# ForceBoard.net
KiCad netlist of a schematic drawn in EAGLE
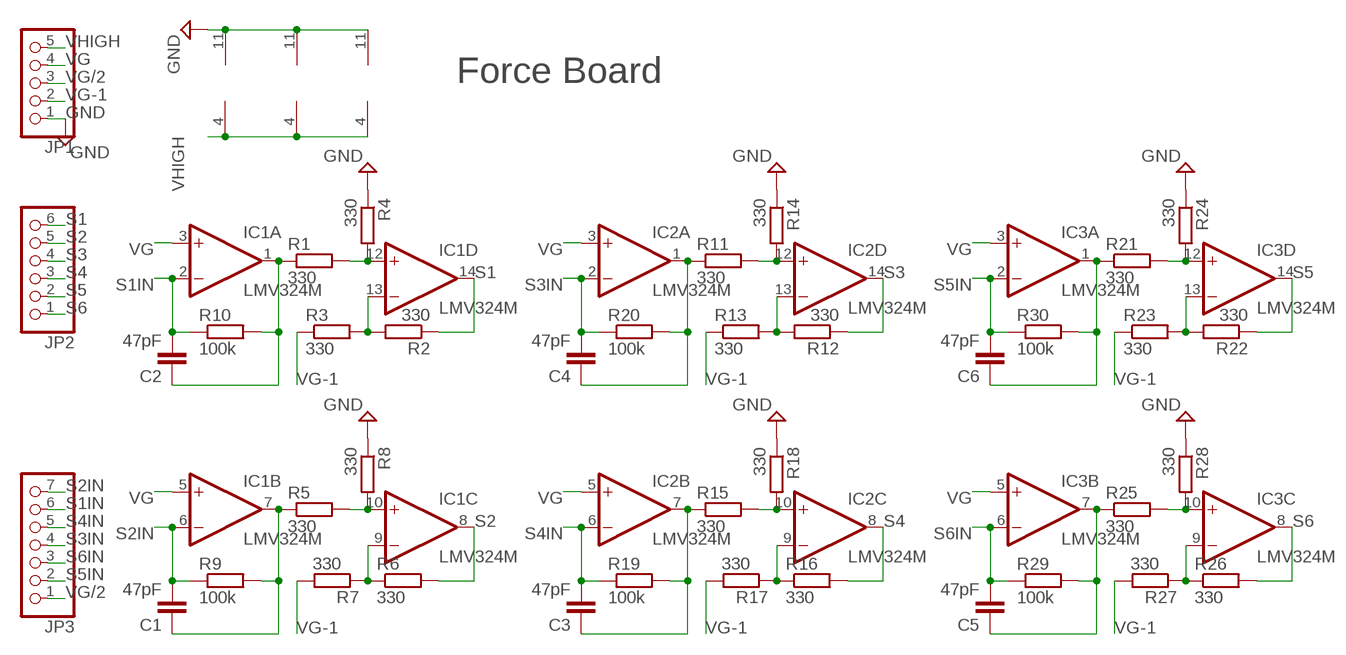
[diagram p0: schematic, sheet 1]

(export (version "E")
  (design (tool "Eeschema 10.0.6"))
  (components
    (comp (ref "C1")
      (value "47pF")
      (footprint "eagle-import:C0805")
      (libsource (lib "eagle-import") (part "C-EUC0805"))
    )
    (comp (ref "C2")
      (value "47pF")
      (footprint "eagle-import:C0805")
      (libsource (lib "eagle-import") (part "C-EUC0805"))
    )
    (comp (ref "C3")
      (value "47pF")
      (footprint "eagle-import:C0805")
      (libsource (lib "eagle-import") (part "C-EUC0805"))
    )
    (comp (ref "C4")
      (value "47pF")
      (footprint "eagle-import:C0805")
      (libsource (lib "eagle-import") (part "C-EUC0805"))
    )
    (comp (ref "C5")
      (value "47pF")
      (footprint "eagle-import:C0805")
      (libsource (lib "eagle-import") (part "C-EUC0805"))
    )
    (comp (ref "C6")
      (value "47pF")
      (footprint "eagle-import:C0805")
      (libsource (lib "eagle-import") (part "C-EUC0805"))
    )
    (comp (ref "IC1")
      (value "LMV324M")
      (footprint "eagle-import:SO14")
      (libsource (lib "eagle-import") (part "LMV324?M"))
    )
    (comp (ref "IC2")
      (value "LMV324M")
      (footprint "eagle-import:SO14")
      (libsource (lib "eagle-import") (part "LMV324?M"))
    )
    (comp (ref "IC3")
      (value "LMV324M")
      (footprint "eagle-import:SO14")
      (libsource (lib "eagle-import") (part "LMV324?M"))
    )
    (comp (ref "JP1")
      (value "PINHD-1X5")
      (footprint "eagle-import:1X05")
      (libsource (lib "eagle-import") (part "PINHD-1X5"))
    )
    (comp (ref "JP2")
      (value "PINHD-1X6")
      (footprint "eagle-import:1X06")
      (libsource (lib "eagle-import") (part "PINHD-1X6"))
    )
    (comp (ref "JP3")
      (value "PINHD-1X7")
      (footprint "eagle-import:1X07")
      (libsource (lib "eagle-import") (part "PINHD-1X7"))
    )
    (comp (ref "R1")
      (value "330")
      (footprint "eagle-import:R0805")
      (libsource (lib "eagle-import") (part "R-EU_R0805"))
    )
    (comp (ref "R2")
      (value "330")
      (footprint "eagle-import:R0805")
      (libsource (lib "eagle-import") (part "R-EU_R0805"))
    )
    (comp (ref "R3")
      (value "330")
      (footprint "eagle-import:R0805")
      (libsource (lib "eagle-import") (part "R-EU_R0805"))
    )
    (comp (ref "R4")
      (value "330")
      (footprint "eagle-import:R0805")
      (libsource (lib "eagle-import") (part "R-EU_R0805"))
    )
    (comp (ref "R5")
      (value "330")
      (footprint "eagle-import:R0805")
      (libsource (lib "eagle-import") (part "R-EU_R0805"))
    )
    (comp (ref "R6")
      (value "330")
      (footprint "eagle-import:R0805")
      (libsource (lib "eagle-import") (part "R-EU_R0805"))
    )
    (comp (ref "R7")
      (value "330")
      (footprint "eagle-import:R0805")
      (libsource (lib "eagle-import") (part "R-EU_R0805"))
    )
    (comp (ref "R8")
      (value "330")
      (footprint "eagle-import:R0805")
      (libsource (lib "eagle-import") (part "R-EU_R0805"))
    )
    (comp (ref "R9")
      (value "100k")
      (footprint "eagle-import:R0805")
      (libsource (lib "eagle-import") (part "R-EU_R0805"))
    )
    (comp (ref "R10")
      (value "100k")
      (footprint "eagle-import:R0805")
      (libsource (lib "eagle-import") (part "R-EU_R0805"))
    )
    (comp (ref "R11")
      (value "330")
      (footprint "eagle-import:R0805")
      (libsource (lib "eagle-import") (part "R-EU_R0805"))
    )
    (comp (ref "R12")
      (value "330")
      (footprint "eagle-import:R0805")
      (libsource (lib "eagle-import") (part "R-EU_R0805"))
    )
    (comp (ref "R13")
      (value "330")
      (footprint "eagle-import:R0805")
      (libsource (lib "eagle-import") (part "R-EU_R0805"))
    )
    (comp (ref "R14")
      (value "330")
      (footprint "eagle-import:R0805")
      (libsource (lib "eagle-import") (part "R-EU_R0805"))
    )
    (comp (ref "R15")
      (value "330")
      (footprint "eagle-import:R0805")
      (libsource (lib "eagle-import") (part "R-EU_R0805"))
    )
    (comp (ref "R16")
      (value "330")
      (footprint "eagle-import:R0805")
      (libsource (lib "eagle-import") (part "R-EU_R0805"))
    )
    (comp (ref "R17")
      (value "330")
      (footprint "eagle-import:R0805")
      (libsource (lib "eagle-import") (part "R-EU_R0805"))
    )
    (comp (ref "R18")
      (value "330")
      (footprint "eagle-import:R0805")
      (libsource (lib "eagle-import") (part "R-EU_R0805"))
    )
    (comp (ref "R19")
      (value "100k")
      (footprint "eagle-import:R0805")
      (libsource (lib "eagle-import") (part "R-EU_R0805"))
    )
    (comp (ref "R20")
      (value "100k")
      (footprint "eagle-import:R0805")
      (libsource (lib "eagle-import") (part "R-EU_R0805"))
    )
    (comp (ref "R21")
      (value "330")
      (footprint "eagle-import:R0805")
      (libsource (lib "eagle-import") (part "R-EU_R0805"))
    )
    (comp (ref "R22")
      (value "330")
      (footprint "eagle-import:R0805")
      (libsource (lib "eagle-import") (part "R-EU_R0805"))
    )
    (comp (ref "R23")
      (value "330")
      (footprint "eagle-import:R0805")
      (libsource (lib "eagle-import") (part "R-EU_R0805"))
    )
    (comp (ref "R24")
      (value "330")
      (footprint "eagle-import:R0805")
      (libsource (lib "eagle-import") (part "R-EU_R0805"))
    )
    (comp (ref "R25")
      (value "330")
      (footprint "eagle-import:R0805")
      (libsource (lib "eagle-import") (part "R-EU_R0805"))
    )
    (comp (ref "R26")
      (value "330")
      (footprint "eagle-import:R0805")
      (libsource (lib "eagle-import") (part "R-EU_R0805"))
    )
    (comp (ref "R27")
      (value "330")
      (footprint "eagle-import:R0805")
      (libsource (lib "eagle-import") (part "R-EU_R0805"))
    )
    (comp (ref "R28")
      (value "330")
      (footprint "eagle-import:R0805")
      (libsource (lib "eagle-import") (part "R-EU_R0805"))
    )
    (comp (ref "R29")
      (value "100k")
      (footprint "eagle-import:R0805")
      (libsource (lib "eagle-import") (part "R-EU_R0805"))
    )
    (comp (ref "R30")
      (value "100k")
      (footprint "eagle-import:R0805")
      (libsource (lib "eagle-import") (part "R-EU_R0805"))
    )
  )
  (nets
    (net (code "1") (name "/S1") (class "Default")
      (node (ref "IC1") (pin "14") (pinfunction "OUT_14") (pintype "output"))
      (node (ref "JP2") (pin "6") (pinfunction "6_6") (pintype "passive"))
      (node (ref "R2") (pin "1") (pinfunction "1_1") (pintype "passive"))
    )
    (net (code "2") (name "/S1IN") (class "Default")
      (node (ref "C2") (pin "2") (pinfunction "2_2") (pintype "passive"))
      (node (ref "IC1") (pin "2") (pinfunction "-IN_2") (pintype "input"))
      (node (ref "JP3") (pin "6") (pinfunction "6_6") (pintype "passive"))
      (node (ref "R10") (pin "1") (pinfunction "1_1") (pintype "passive"))
    )
    (net (code "3") (name "/S2") (class "Default")
      (node (ref "IC1") (pin "8") (pinfunction "OUT_8") (pintype "output"))
      (node (ref "JP2") (pin "5") (pinfunction "5_5") (pintype "passive"))
      (node (ref "R6") (pin "2") (pinfunction "2_2") (pintype "passive"))
    )
    (net (code "4") (name "/S2IN") (class "Default")
      (node (ref "C1") (pin "2") (pinfunction "2_2") (pintype "passive"))
      (node (ref "IC1") (pin "6") (pinfunction "-IN_6") (pintype "input"))
      (node (ref "JP3") (pin "7") (pinfunction "7_7") (pintype "passive"))
      (node (ref "R9") (pin "1") (pinfunction "1_1") (pintype "passive"))
    )
    (net (code "5") (name "/S3") (class "Default")
      (node (ref "IC2") (pin "14") (pinfunction "OUT_14") (pintype "output"))
      (node (ref "JP2") (pin "4") (pinfunction "4_4") (pintype "passive"))
      (node (ref "R12") (pin "1") (pinfunction "1_1") (pintype "passive"))
    )
    (net (code "6") (name "/S3IN") (class "Default")
      (node (ref "C4") (pin "2") (pinfunction "2_2") (pintype "passive"))
      (node (ref "IC2") (pin "2") (pinfunction "-IN_2") (pintype "input"))
      (node (ref "JP3") (pin "4") (pinfunction "4_4") (pintype "passive"))
      (node (ref "R20") (pin "1") (pinfunction "1_1") (pintype "passive"))
    )
    (net (code "7") (name "/S4") (class "Default")
      (node (ref "IC2") (pin "8") (pinfunction "OUT_8") (pintype "output"))
      (node (ref "JP2") (pin "3") (pinfunction "3_3") (pintype "passive"))
      (node (ref "R16") (pin "2") (pinfunction "2_2") (pintype "passive"))
    )
    (net (code "8") (name "/S4IN") (class "Default")
      (node (ref "C3") (pin "2") (pinfunction "2_2") (pintype "passive"))
      (node (ref "IC2") (pin "6") (pinfunction "-IN_6") (pintype "input"))
      (node (ref "JP3") (pin "5") (pinfunction "5_5") (pintype "passive"))
      (node (ref "R19") (pin "1") (pinfunction "1_1") (pintype "passive"))
    )
    (net (code "9") (name "/S5") (class "Default")
      (node (ref "IC3") (pin "14") (pinfunction "OUT_14") (pintype "output"))
      (node (ref "JP2") (pin "2") (pinfunction "2_2") (pintype "passive"))
      (node (ref "R22") (pin "1") (pinfunction "1_1") (pintype "passive"))
    )
    (net (code "10") (name "/S5IN") (class "Default")
      (node (ref "C6") (pin "2") (pinfunction "2_2") (pintype "passive"))
      (node (ref "IC3") (pin "2") (pinfunction "-IN_2") (pintype "input"))
      (node (ref "JP3") (pin "2") (pinfunction "2_2") (pintype "passive"))
      (node (ref "R30") (pin "1") (pinfunction "1_1") (pintype "passive"))
    )
    (net (code "11") (name "/S6") (class "Default")
      (node (ref "IC3") (pin "8") (pinfunction "OUT_8") (pintype "output"))
      (node (ref "JP2") (pin "1") (pinfunction "1_1") (pintype "passive"))
      (node (ref "R26") (pin "2") (pinfunction "2_2") (pintype "passive"))
    )
    (net (code "12") (name "/S6IN") (class "Default")
      (node (ref "C5") (pin "2") (pinfunction "2_2") (pintype "passive"))
      (node (ref "IC3") (pin "6") (pinfunction "-IN_6") (pintype "input"))
      (node (ref "JP3") (pin "3") (pinfunction "3_3") (pintype "passive"))
      (node (ref "R29") (pin "1") (pinfunction "1_1") (pintype "passive"))
    )
    (net (code "13") (name "/VG") (class "Default")
      (node (ref "IC1") (pin "3") (pinfunction "+IN_3") (pintype "input"))
      (node (ref "IC1") (pin "5") (pinfunction "+IN_5") (pintype "input"))
      (node (ref "IC2") (pin "3") (pinfunction "+IN_3") (pintype "input"))
      (node (ref "IC2") (pin "5") (pinfunction "+IN_5") (pintype "input"))
      (node (ref "IC3") (pin "3") (pinfunction "+IN_3") (pintype "input"))
      (node (ref "IC3") (pin "5") (pinfunction "+IN_5") (pintype "input"))
      (node (ref "JP1") (pin "4") (pinfunction "4_4") (pintype "passive"))
    )
    (net (code "14") (name "/VG-1") (class "Default")
      (node (ref "JP1") (pin "2") (pinfunction "2_2") (pintype "passive"))
      (node (ref "R13") (pin "1") (pinfunction "1_1") (pintype "passive"))
      (node (ref "R17") (pin "2") (pinfunction "2_2") (pintype "passive"))
      (node (ref "R23") (pin "1") (pinfunction "1_1") (pintype "passive"))
      (node (ref "R27") (pin "2") (pinfunction "2_2") (pintype "passive"))
      (node (ref "R3") (pin "1") (pinfunction "1_1") (pintype "passive"))
      (node (ref "R7") (pin "2") (pinfunction "2_2") (pintype "passive"))
    )
    (net (code "15") (name "/VG{slash}2") (class "Default")
      (node (ref "JP1") (pin "3") (pinfunction "3_3") (pintype "passive"))
      (node (ref "JP3") (pin "1") (pinfunction "1_1") (pintype "passive"))
    )
    (net (code "16") (name "/VHIGH") (class "Default")
      (node (ref "IC1") (pin "4") (pinfunction "V+_4") (pintype "power_in"))
      (node (ref "IC2") (pin "4") (pinfunction "V+_4") (pintype "power_in"))
      (node (ref "IC3") (pin "4") (pinfunction "V+_4") (pintype "power_in"))
      (node (ref "JP1") (pin "5") (pinfunction "5_5") (pintype "passive"))
    )
    (net (code "17") (name "GND") (class "Default")
      (node (ref "IC1") (pin "11") (pinfunction "V-_11") (pintype "power_in"))
      (node (ref "IC2") (pin "11") (pinfunction "V-_11") (pintype "power_in"))
      (node (ref "IC3") (pin "11") (pinfunction "V-_11") (pintype "power_in"))
      (node (ref "JP1") (pin "1") (pinfunction "1_1") (pintype "passive"))
      (node (ref "R14") (pin "1") (pinfunction "1_1") (pintype "passive"))
      (node (ref "R18") (pin "1") (pinfunction "1_1") (pintype "passive"))
      (node (ref "R24") (pin "1") (pinfunction "1_1") (pintype "passive"))
      (node (ref "R28") (pin "1") (pinfunction "1_1") (pintype "passive"))
      (node (ref "R4") (pin "1") (pinfunction "1_1") (pintype "passive"))
      (node (ref "R8") (pin "1") (pinfunction "1_1") (pintype "passive"))
    )
    (net (code "18") (name "Net-(IC1A-OUT)") (class "Default")
      (node (ref "C2") (pin "1") (pinfunction "1_1") (pintype "passive"))
      (node (ref "IC1") (pin "1") (pinfunction "OUT_1") (pintype "output"))
      (node (ref "R1") (pin "1") (pinfunction "1_1") (pintype "passive"))
      (node (ref "R10") (pin "2") (pinfunction "2_2") (pintype "passive"))
    )
    (net (code "19") (name "Net-(IC1B-OUT)") (class "Default")
      (node (ref "C1") (pin "1") (pinfunction "1_1") (pintype "passive"))
      (node (ref "IC1") (pin "7") (pinfunction "OUT_7") (pintype "output"))
      (node (ref "R5") (pin "1") (pinfunction "1_1") (pintype "passive"))
      (node (ref "R9") (pin "2") (pinfunction "2_2") (pintype "passive"))
    )
    (net (code "20") (name "Net-(IC1C-+IN)") (class "Default")
      (node (ref "IC1") (pin "10") (pinfunction "+IN_10") (pintype "input"))
      (node (ref "R5") (pin "2") (pinfunction "2_2") (pintype "passive"))
      (node (ref "R8") (pin "2") (pinfunction "2_2") (pintype "passive"))
    )
    (net (code "21") (name "Net-(IC1C--IN)") (class "Default")
      (node (ref "IC1") (pin "9") (pinfunction "-IN_9") (pintype "input"))
      (node (ref "R6") (pin "1") (pinfunction "1_1") (pintype "passive"))
      (node (ref "R7") (pin "1") (pinfunction "1_1") (pintype "passive"))
    )
    (net (code "22") (name "Net-(IC1D-+IN)") (class "Default")
      (node (ref "IC1") (pin "12") (pinfunction "+IN_12") (pintype "input"))
      (node (ref "R1") (pin "2") (pinfunction "2_2") (pintype "passive"))
      (node (ref "R4") (pin "2") (pinfunction "2_2") (pintype "passive"))
    )
    (net (code "23") (name "Net-(IC1D--IN)") (class "Default")
      (node (ref "IC1") (pin "13") (pinfunction "-IN_13") (pintype "input"))
      (node (ref "R2") (pin "2") (pinfunction "2_2") (pintype "passive"))
      (node (ref "R3") (pin "2") (pinfunction "2_2") (pintype "passive"))
    )
    (net (code "24") (name "Net-(IC2A-OUT)") (class "Default")
      (node (ref "C4") (pin "1") (pinfunction "1_1") (pintype "passive"))
      (node (ref "IC2") (pin "1") (pinfunction "OUT_1") (pintype "output"))
      (node (ref "R11") (pin "1") (pinfunction "1_1") (pintype "passive"))
      (node (ref "R20") (pin "2") (pinfunction "2_2") (pintype "passive"))
    )
    (net (code "25") (name "Net-(IC2B-OUT)") (class "Default")
      (node (ref "C3") (pin "1") (pinfunction "1_1") (pintype "passive"))
      (node (ref "IC2") (pin "7") (pinfunction "OUT_7") (pintype "output"))
      (node (ref "R15") (pin "1") (pinfunction "1_1") (pintype "passive"))
      (node (ref "R19") (pin "2") (pinfunction "2_2") (pintype "passive"))
    )
    (net (code "26") (name "Net-(IC2C-+IN)") (class "Default")
      (node (ref "IC2") (pin "10") (pinfunction "+IN_10") (pintype "input"))
      (node (ref "R15") (pin "2") (pinfunction "2_2") (pintype "passive"))
      (node (ref "R18") (pin "2") (pinfunction "2_2") (pintype "passive"))
    )
    (net (code "27") (name "Net-(IC2C--IN)") (class "Default")
      (node (ref "IC2") (pin "9") (pinfunction "-IN_9") (pintype "input"))
      (node (ref "R16") (pin "1") (pinfunction "1_1") (pintype "passive"))
      (node (ref "R17") (pin "1") (pinfunction "1_1") (pintype "passive"))
    )
    (net (code "28") (name "Net-(IC2D-+IN)") (class "Default")
      (node (ref "IC2") (pin "12") (pinfunction "+IN_12") (pintype "input"))
      (node (ref "R11") (pin "2") (pinfunction "2_2") (pintype "passive"))
      (node (ref "R14") (pin "2") (pinfunction "2_2") (pintype "passive"))
    )
    (net (code "29") (name "Net-(IC2D--IN)") (class "Default")
      (node (ref "IC2") (pin "13") (pinfunction "-IN_13") (pintype "input"))
      (node (ref "R12") (pin "2") (pinfunction "2_2") (pintype "passive"))
      (node (ref "R13") (pin "2") (pinfunction "2_2") (pintype "passive"))
    )
    (net (code "30") (name "Net-(IC3A-OUT)") (class "Default")
      (node (ref "C6") (pin "1") (pinfunction "1_1") (pintype "passive"))
      (node (ref "IC3") (pin "1") (pinfunction "OUT_1") (pintype "output"))
      (node (ref "R21") (pin "1") (pinfunction "1_1") (pintype "passive"))
      (node (ref "R30") (pin "2") (pinfunction "2_2") (pintype "passive"))
    )
    (net (code "31") (name "Net-(IC3B-OUT)") (class "Default")
      (node (ref "C5") (pin "1") (pinfunction "1_1") (pintype "passive"))
      (node (ref "IC3") (pin "7") (pinfunction "OUT_7") (pintype "output"))
      (node (ref "R25") (pin "1") (pinfunction "1_1") (pintype "passive"))
      (node (ref "R29") (pin "2") (pinfunction "2_2") (pintype "passive"))
    )
    (net (code "32") (name "Net-(IC3C-+IN)") (class "Default")
      (node (ref "IC3") (pin "10") (pinfunction "+IN_10") (pintype "input"))
      (node (ref "R25") (pin "2") (pinfunction "2_2") (pintype "passive"))
      (node (ref "R28") (pin "2") (pinfunction "2_2") (pintype "passive"))
    )
    (net (code "33") (name "Net-(IC3C--IN)") (class "Default")
      (node (ref "IC3") (pin "9") (pinfunction "-IN_9") (pintype "input"))
      (node (ref "R26") (pin "1") (pinfunction "1_1") (pintype "passive"))
      (node (ref "R27") (pin "1") (pinfunction "1_1") (pintype "passive"))
    )
    (net (code "34") (name "Net-(IC3D-+IN)") (class "Default")
      (node (ref "IC3") (pin "12") (pinfunction "+IN_12") (pintype "input"))
      (node (ref "R21") (pin "2") (pinfunction "2_2") (pintype "passive"))
      (node (ref "R24") (pin "2") (pinfunction "2_2") (pintype "passive"))
    )
    (net (code "35") (name "Net-(IC3D--IN)") (class "Default")
      (node (ref "IC3") (pin "13") (pinfunction "-IN_13") (pintype "input"))
      (node (ref "R22") (pin "2") (pinfunction "2_2") (pintype "passive"))
      (node (ref "R23") (pin "2") (pinfunction "2_2") (pintype "passive"))
    )
  )
)
